# Schematic_DEBUGGER.net
KiCad netlist of a schematic drawn in Altium Designer
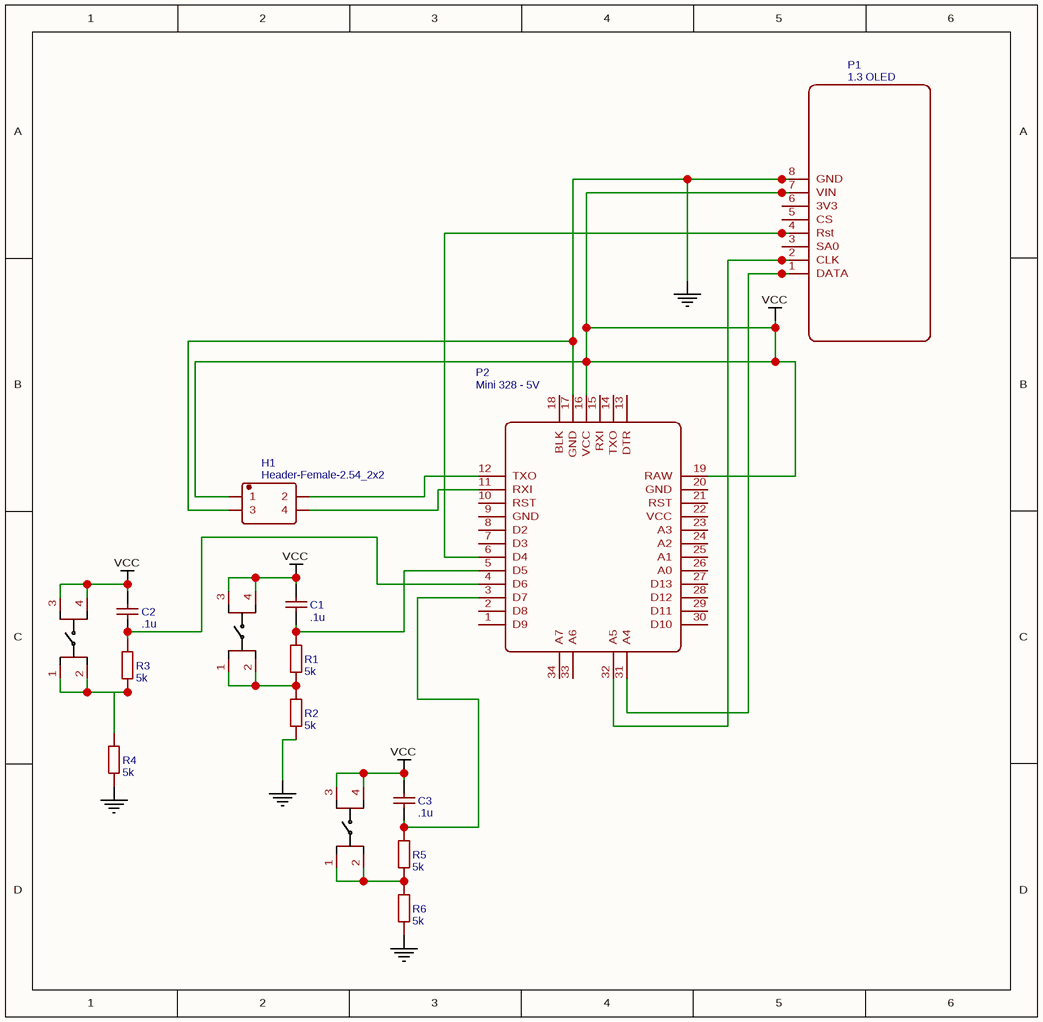
[diagram p0: Schematic_DEBUGGER.schdoc]

(export (version "E")
  (design (tool "Eeschema 10.0.6"))
  (components
    (comp (ref "B1")
      (value "TS-1102-5016")
      (fields (field (name "BOM_SUPPLIER PART") "C111609") (field (name "CONTRIBUTOR") "EasyEDA"))
      (libsource (lib "altium-import") (part "root_1_TS-1102-5016_"))
    )
    (comp (ref "B2")
      (value "TS-1102-5016")
      (fields (field (name "BOM_SUPPLIER PART") "C111609") (field (name "CONTRIBUTOR") "EasyEDA"))
      (libsource (lib "altium-import") (part "root_1_TS-1102-5016_"))
    )
    (comp (ref "B3")
      (value "TS-1102-5016")
      (fields (field (name "BOM_SUPPLIER PART") "C111609") (field (name "CONTRIBUTOR") "EasyEDA"))
      (libsource (lib "altium-import") (part "root_1_TS-1102-5016_"))
    )
    (comp (ref "C1")
      (value ".1u")
      (fields
        (field (name "BOM_MANUFACTURER PART") "Ceramic capacitors47PF 3KV")
        (field (name "BOM_SUPPLIER PART") "C19375")
        (field (name "CONTRIBUTOR") "LCSC")
      )
      (libsource (lib "altium-import") (part "root_1_.1u_"))
    )
    (comp (ref "C2")
      (value ".1u")
      (fields
        (field (name "BOM_MANUFACTURER PART") "Ceramic capacitors47PF 3KV")
        (field (name "BOM_SUPPLIER PART") "C19375")
        (field (name "CONTRIBUTOR") "LCSC")
      )
      (libsource (lib "altium-import") (part "root_1_.1u_"))
    )
    (comp (ref "C3")
      (value ".1u")
      (fields
        (field (name "BOM_MANUFACTURER PART") "Ceramic capacitors47PF 3KV")
        (field (name "BOM_SUPPLIER PART") "C19375")
        (field (name "CONTRIBUTOR") "LCSC")
      )
      (libsource (lib "altium-import") (part "root_1_.1u_"))
    )
    (comp (ref "H1")
      (value "Header-Female-2.54_2x2")
      (fields
        (field (name "BOM_MANUFACTURER PART") "DS1023-2*2SF11")
        (field (name "BOM_SUPPLIER PART") "C92273")
        (field (name "CONTRIBUTOR") "LCSC")
      )
      (libsource (lib "altium-import") (part "root_0_Header-Female-2.54_2x2_"))
    )
    (comp (ref "P1")
      (value "1.3 OLED")
      (fields (field (name "BOM_SUPPLIER PART") "undefined") (field (name "BOM_MANUFACTURER PART") "?"))
      (libsource (lib "altium-import") (part "root_1_1.3 OLED_"))
    )
    (comp (ref "P2")
      (value "Mini 328 - 5V")
      (fields (field (name "BOM_MANUFACTURER PART") "?"))
      (libsource (lib "altium-import") (part "root_0_Mini 328 - 5V_"))
    )
    (comp (ref "R1")
      (value "5k")
      (fields (field (name "BOM_MANUFACTURER PART") "?"))
      (libsource (lib "altium-import") (part "root_1_5k_"))
    )
    (comp (ref "R2")
      (value "5k")
      (fields (field (name "BOM_MANUFACTURER PART") "?"))
      (libsource (lib "altium-import") (part "root_1_5k_"))
    )
    (comp (ref "R3")
      (value "5k")
      (fields (field (name "BOM_MANUFACTURER PART") "?"))
      (libsource (lib "altium-import") (part "root_1_5k_"))
    )
    (comp (ref "R4")
      (value "5k")
      (fields (field (name "BOM_MANUFACTURER PART") "?"))
      (libsource (lib "altium-import") (part "root_1_5k_"))
    )
    (comp (ref "R5")
      (value "5k")
      (fields (field (name "BOM_MANUFACTURER PART") "?"))
      (libsource (lib "altium-import") (part "root_1_5k_"))
    )
    (comp (ref "R6")
      (value "5k")
      (fields (field (name "BOM_MANUFACTURER PART") "?"))
      (libsource (lib "altium-import") (part "root_1_5k_"))
    )
  )
  (nets
    (net (code "1") (name "GND") (class "Default")
      (node (ref "H1") (pin "3") (pinfunction "3_3") (pintype "passive"))
      (node (ref "P1") (pin "8") (pinfunction "GND_8") (pintype "passive"))
      (node (ref "P2") (pin "17") (pinfunction "GND_17") (pintype "passive"))
      (node (ref "R2") (pin "1") (pinfunction "1_1") (pintype "passive"))
      (node (ref "R4") (pin "1") (pinfunction "1_1") (pintype "passive"))
      (node (ref "R6") (pin "1") (pinfunction "1_1") (pintype "passive"))
    )
    (net (code "2") (name "Net-(B1-Pad1)") (class "Default")
      (node (ref "B1") (pin "1") (pinfunction "1_1") (pintype "passive"))
      (node (ref "B1") (pin "2") (pinfunction "2_2") (pintype "passive"))
      (node (ref "R1") (pin "1") (pinfunction "1_1") (pintype "passive"))
      (node (ref "R2") (pin "2") (pinfunction "2_2") (pintype "passive"))
    )
    (net (code "3") (name "Net-(B2-Pad1)") (class "Default")
      (node (ref "B2") (pin "1") (pinfunction "1_1") (pintype "passive"))
      (node (ref "B2") (pin "2") (pinfunction "2_2") (pintype "passive"))
      (node (ref "R3") (pin "1") (pinfunction "1_1") (pintype "passive"))
      (node (ref "R4") (pin "2") (pinfunction "2_2") (pintype "passive"))
    )
    (net (code "4") (name "Net-(B3-Pad1)") (class "Default")
      (node (ref "B3") (pin "1") (pinfunction "1_1") (pintype "passive"))
      (node (ref "B3") (pin "2") (pinfunction "2_2") (pintype "passive"))
      (node (ref "R5") (pin "1") (pinfunction "1_1") (pintype "passive"))
      (node (ref "R6") (pin "2") (pinfunction "2_2") (pintype "passive"))
    )
    (net (code "5") (name "Net-(H1-Pad2)") (class "Default")
      (node (ref "H1") (pin "2") (pinfunction "2_2") (pintype "passive"))
      (node (ref "P2") (pin "12") (pinfunction "TXO_12") (pintype "passive"))
    )
    (net (code "6") (name "Net-(H1-Pad4)") (class "Default")
      (node (ref "H1") (pin "4") (pinfunction "4_4") (pintype "passive"))
      (node (ref "P2") (pin "11") (pinfunction "RXI_11") (pintype "passive"))
    )
    (net (code "7") (name "Net-(P1-CLK)") (class "Default")
      (node (ref "P1") (pin "2") (pinfunction "CLK_2") (pintype "passive"))
      (node (ref "P2") (pin "32") (pinfunction "A5_32") (pintype "passive"))
    )
    (net (code "8") (name "Net-(P1-DATA)") (class "Default")
      (node (ref "P1") (pin "1") (pinfunction "DATA_1") (pintype "passive"))
      (node (ref "P2") (pin "31") (pinfunction "A4_31") (pintype "passive"))
    )
    (net (code "9") (name "Net-(P1-Rst)") (class "Default")
      (node (ref "P1") (pin "4") (pinfunction "Rst_4") (pintype "passive"))
      (node (ref "P2") (pin "6") (pinfunction "D4_6") (pintype "passive"))
    )
    (net (code "10") (name "Net-(P2-D5)") (class "Default")
      (node (ref "C1") (pin "1") (pinfunction "1_1") (pintype "passive"))
      (node (ref "P2") (pin "5") (pinfunction "D5_5") (pintype "passive"))
      (node (ref "R1") (pin "2") (pinfunction "2_2") (pintype "passive"))
    )
    (net (code "11") (name "Net-(P2-D6)") (class "Default")
      (node (ref "C2") (pin "1") (pinfunction "1_1") (pintype "passive"))
      (node (ref "P2") (pin "4") (pinfunction "D6_4") (pintype "passive"))
      (node (ref "R3") (pin "2") (pinfunction "2_2") (pintype "passive"))
    )
    (net (code "12") (name "Net-(P2-D7)") (class "Default")
      (node (ref "C3") (pin "1") (pinfunction "1_1") (pintype "passive"))
      (node (ref "P2") (pin "3") (pinfunction "D7_3") (pintype "passive"))
      (node (ref "R5") (pin "2") (pinfunction "2_2") (pintype "passive"))
    )
    (net (code "13") (name "VCC") (class "Default")
      (node (ref "B1") (pin "3") (pinfunction "3_3") (pintype "passive"))
      (node (ref "B1") (pin "4") (pinfunction "4_4") (pintype "passive"))
      (node (ref "B2") (pin "3") (pinfunction "3_3") (pintype "passive"))
      (node (ref "B2") (pin "4") (pinfunction "4_4") (pintype "passive"))
      (node (ref "B3") (pin "3") (pinfunction "3_3") (pintype "passive"))
      (node (ref "B3") (pin "4") (pinfunction "4_4") (pintype "passive"))
      (node (ref "C1") (pin "2") (pinfunction "2_2") (pintype "passive"))
      (node (ref "C2") (pin "2") (pinfunction "2_2") (pintype "passive"))
      (node (ref "C3") (pin "2") (pinfunction "2_2") (pintype "passive"))
      (node (ref "H1") (pin "1") (pinfunction "1_1") (pintype "passive"))
      (node (ref "P1") (pin "7") (pinfunction "VIN_7") (pintype "passive"))
      (node (ref "P2") (pin "16") (pinfunction "VCC_16") (pintype "passive"))
      (node (ref "P2") (pin "19") (pinfunction "RAW_19") (pintype "passive"))
    )
    (net (code "14") (name "unconnected-(P1-3V3-Pad6)") (class "Default")
      (node (ref "P1") (pin "6") (pinfunction "3V3_6") (pintype "passive"))
    )
    (net (code "15") (name "unconnected-(P1-CS-Pad5)") (class "Default")
      (node (ref "P1") (pin "5") (pinfunction "CS_5") (pintype "passive"))
    )
    (net (code "16") (name "unconnected-(P1-SA0-Pad3)") (class "Default")
      (node (ref "P1") (pin "3") (pinfunction "SA0_3") (pintype "passive"))
    )
    (net (code "17") (name "unconnected-(P2-A0-Pad26)") (class "Default")
      (node (ref "P2") (pin "26") (pinfunction "A0_26") (pintype "passive"))
    )
    (net (code "18") (name "unconnected-(P2-A1-Pad25)") (class "Default")
      (node (ref "P2") (pin "25") (pinfunction "A1_25") (pintype "passive"))
    )
    (net (code "19") (name "unconnected-(P2-A2-Pad24)") (class "Default")
      (node (ref "P2") (pin "24") (pinfunction "A2_24") (pintype "passive"))
    )
    (net (code "20") (name "unconnected-(P2-A3-Pad23)") (class "Default")
      (node (ref "P2") (pin "23") (pinfunction "A3_23") (pintype "passive"))
    )
    (net (code "21") (name "unconnected-(P2-A6-Pad33)") (class "Default")
      (node (ref "P2") (pin "33") (pinfunction "A6_33") (pintype "passive"))
    )
    (net (code "22") (name "unconnected-(P2-A7-Pad34)") (class "Default")
      (node (ref "P2") (pin "34") (pinfunction "A7_34") (pintype "passive"))
    )
    (net (code "23") (name "unconnected-(P2-BLK-Pad18)") (class "Default")
      (node (ref "P2") (pin "18") (pinfunction "BLK_18") (pintype "passive"))
    )
    (net (code "24") (name "unconnected-(P2-D2-Pad8)") (class "Default")
      (node (ref "P2") (pin "8") (pinfunction "D2_8") (pintype "passive"))
    )
    (net (code "25") (name "unconnected-(P2-D3-Pad7)") (class "Default")
      (node (ref "P2") (pin "7") (pinfunction "D3_7") (pintype "passive"))
    )
    (net (code "26") (name "unconnected-(P2-D8-Pad2)") (class "Default")
      (node (ref "P2") (pin "2") (pinfunction "D8_2") (pintype "passive"))
    )
    (net (code "27") (name "unconnected-(P2-D9-Pad1)") (class "Default")
      (node (ref "P2") (pin "1") (pinfunction "D9_1") (pintype "passive"))
    )
    (net (code "28") (name "unconnected-(P2-D10-Pad30)") (class "Default")
      (node (ref "P2") (pin "30") (pinfunction "D10_30") (pintype "passive"))
    )
    (net (code "29") (name "unconnected-(P2-D11-Pad29)") (class "Default")
      (node (ref "P2") (pin "29") (pinfunction "D11_29") (pintype "passive"))
    )
    (net (code "30") (name "unconnected-(P2-D12-Pad28)") (class "Default")
      (node (ref "P2") (pin "28") (pinfunction "D12_28") (pintype "passive"))
    )
    (net (code "31") (name "unconnected-(P2-D13-Pad27)") (class "Default")
      (node (ref "P2") (pin "27") (pinfunction "D13_27") (pintype "passive"))
    )
    (net (code "32") (name "unconnected-(P2-DTR-Pad13)") (class "Default")
      (node (ref "P2") (pin "13") (pinfunction "DTR_13") (pintype "passive"))
    )
    (net (code "33") (name "unconnected-(P2-GND-Pad9)") (class "Default")
      (node (ref "P2") (pin "9") (pinfunction "GND_9") (pintype "passive"))
    )
    (net (code "34") (name "unconnected-(P2-GND-Pad20)") (class "Default")
      (node (ref "P2") (pin "20") (pinfunction "GND_20") (pintype "passive"))
    )
    (net (code "35") (name "unconnected-(P2-RST-Pad10)") (class "Default")
      (node (ref "P2") (pin "10") (pinfunction "RST_10") (pintype "passive"))
    )
    (net (code "36") (name "unconnected-(P2-RST-Pad21)") (class "Default")
      (node (ref "P2") (pin "21") (pinfunction "RST_21") (pintype "passive"))
    )
    (net (code "37") (name "unconnected-(P2-RXI-Pad15)") (class "Default")
      (node (ref "P2") (pin "15") (pinfunction "RXI_15") (pintype "passive"))
    )
    (net (code "38") (name "unconnected-(P2-TXO-Pad14)") (class "Default")
      (node (ref "P2") (pin "14") (pinfunction "TXO_14") (pintype "passive"))
    )
    (net (code "39") (name "unconnected-(P2-VCC-Pad22)") (class "Default")
      (node (ref "P2") (pin "22") (pinfunction "VCC_22") (pintype "passive"))
    )
  )
)
